# PrototypeVar2_IcChanged.net
KiCad netlist of a schematic drawn in EAGLE
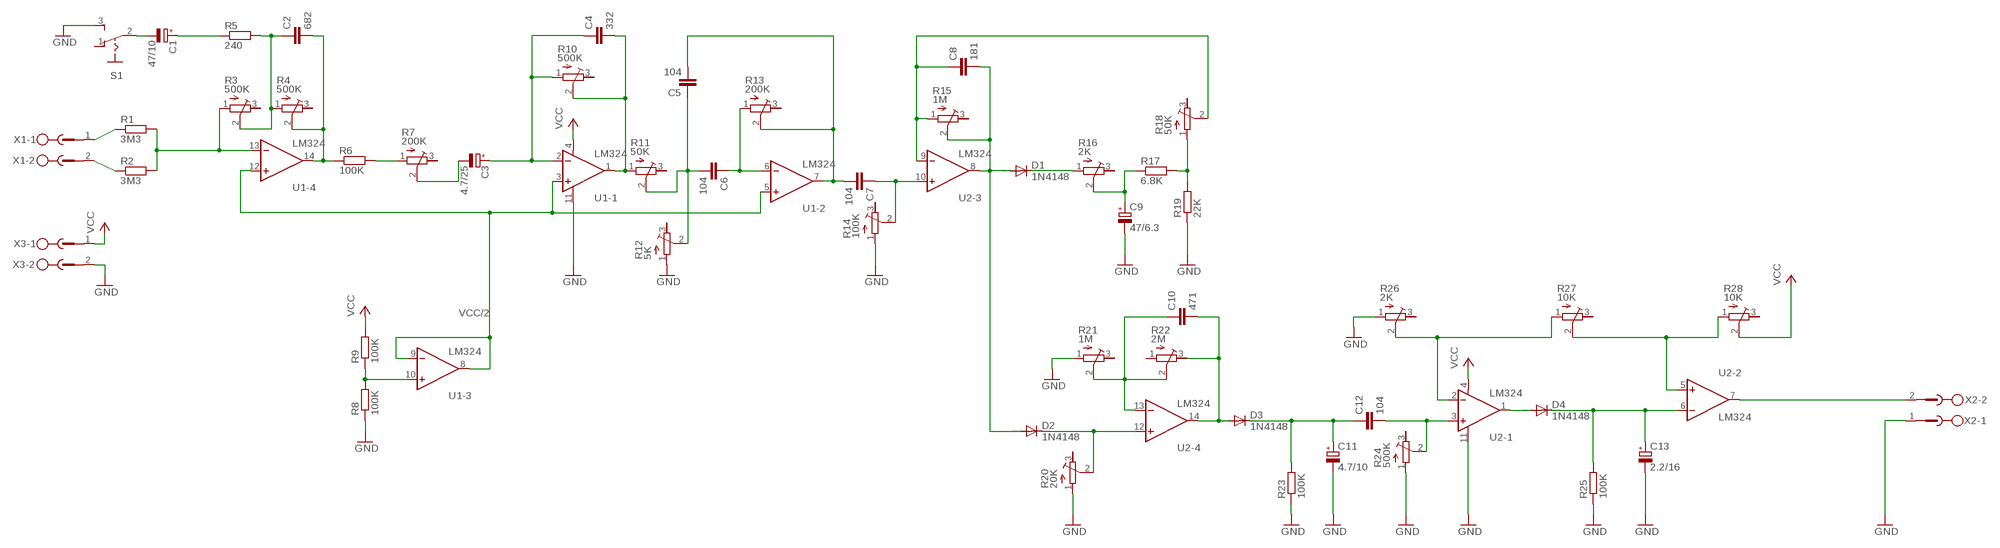
[diagram p0: schematic, sheet 1]

(export (version "E")
  (design (tool "Eeschema 10.0.6"))
  (components
    (comp (ref "C1")
      (value "47/10")
      (footprint "eagle-import:E2,5-7")
      (libsource (lib "eagle-import") (part "CPOL-EUE2.5-7"))
    )
    (comp (ref "C2")
      (value "682")
      (footprint "eagle-import:C050-035X075")
      (libsource (lib "eagle-import") (part "C-EU050-035X075"))
    )
    (comp (ref "C3")
      (value "4.7/25")
      (footprint "eagle-import:E2,5-7")
      (libsource (lib "eagle-import") (part "CPOL-EUE2.5-7"))
    )
    (comp (ref "C4")
      (value "332")
      (footprint "eagle-import:C050-035X075")
      (libsource (lib "eagle-import") (part "C-EU050-035X075"))
    )
    (comp (ref "C5")
      (value "104")
      (footprint "eagle-import:C050-035X075")
      (libsource (lib "eagle-import") (part "C-EU050-035X075"))
    )
    (comp (ref "C6")
      (value "104")
      (footprint "eagle-import:C050-035X075")
      (libsource (lib "eagle-import") (part "C-EU050-035X075"))
    )
    (comp (ref "C7")
      (value "104")
      (footprint "eagle-import:C050-035X075")
      (libsource (lib "eagle-import") (part "C-EU050-035X075"))
    )
    (comp (ref "C8")
      (value "181")
      (footprint "eagle-import:C050-035X075")
      (libsource (lib "eagle-import") (part "C-EU050-035X075"))
    )
    (comp (ref "C9")
      (value "47/6.3")
      (footprint "eagle-import:E2,5-7")
      (libsource (lib "eagle-import") (part "CPOL-EUE2.5-7"))
    )
    (comp (ref "C10")
      (value "471")
      (footprint "eagle-import:C050-035X075")
      (libsource (lib "eagle-import") (part "C-EU050-035X075"))
    )
    (comp (ref "C11")
      (value "4.7/10")
      (footprint "eagle-import:E2,5-7")
      (libsource (lib "eagle-import") (part "CPOL-EUE2.5-7"))
    )
    (comp (ref "C12")
      (value "104")
      (footprint "eagle-import:C050-035X075")
      (libsource (lib "eagle-import") (part "C-EU050-035X075"))
    )
    (comp (ref "C13")
      (value "2.2/16")
      (footprint "eagle-import:E2,5-7")
      (libsource (lib "eagle-import") (part "CPOL-EUE2.5-7"))
    )
    (comp (ref "D1")
      (value "1N4148")
      (footprint "eagle-import:DO35-10")
      (libsource (lib "eagle-import") (part "1N4148DO35-10"))
    )
    (comp (ref "D2")
      (value "1N4148")
      (footprint "eagle-import:DO35-10")
      (libsource (lib "eagle-import") (part "1N4148DO35-10"))
    )
    (comp (ref "D3")
      (value "1N4148")
      (footprint "eagle-import:DO35-10")
      (libsource (lib "eagle-import") (part "1N4148DO35-10"))
    )
    (comp (ref "D4")
      (value "1N4148")
      (footprint "eagle-import:DO35-10")
      (libsource (lib "eagle-import") (part "1N4148DO35-10"))
    )
    (comp (ref "R1")
      (value "3M3")
      (footprint "eagle-import:0204_7")
      (libsource (lib "eagle-import") (part "R-EU_0204/7"))
    )
    (comp (ref "R2")
      (value "3M3")
      (footprint "eagle-import:0204_7")
      (libsource (lib "eagle-import") (part "R-EU_0204/7"))
    )
    (comp (ref "R3")
      (value "500K")
      (footprint "eagle-import:RTRIM64W")
      (libsource (lib "eagle-import") (part "R-TRIMM64W"))
    )
    (comp (ref "R4")
      (value "500K")
      (footprint "eagle-import:RTRIM64W")
      (libsource (lib "eagle-import") (part "R-TRIMM64W"))
    )
    (comp (ref "R5")
      (value "240")
      (footprint "eagle-import:0204_7")
      (libsource (lib "eagle-import") (part "R-EU_0204/7"))
    )
    (comp (ref "R6")
      (value "100K")
      (footprint "eagle-import:0204_7")
      (libsource (lib "eagle-import") (part "R-EU_0204/7"))
    )
    (comp (ref "R7")
      (value "200K")
      (footprint "eagle-import:RTRIM64W")
      (libsource (lib "eagle-import") (part "R-TRIMM64W"))
    )
    (comp (ref "R8")
      (value "100K")
      (footprint "eagle-import:0207_10")
      (libsource (lib "eagle-import") (part "R-EU_0207/10"))
    )
    (comp (ref "R9")
      (value "100K")
      (footprint "eagle-import:0207_10")
      (libsource (lib "eagle-import") (part "R-EU_0207/10"))
    )
    (comp (ref "R10")
      (value "500K")
      (footprint "eagle-import:RTRIM64W")
      (libsource (lib "eagle-import") (part "R-TRIMM64W"))
    )
    (comp (ref "R11")
      (value "50K")
      (footprint "eagle-import:RTRIM64W")
      (libsource (lib "eagle-import") (part "R-TRIMM64W"))
    )
    (comp (ref "R12")
      (value "5K")
      (footprint "eagle-import:RTRIM64W")
      (libsource (lib "eagle-import") (part "R-TRIMM64W"))
    )
    (comp (ref "R13")
      (value "200K")
      (footprint "eagle-import:RTRIM64W")
      (libsource (lib "eagle-import") (part "R-TRIMM64W"))
    )
    (comp (ref "R14")
      (value "100K")
      (footprint "eagle-import:RTRIM64W")
      (libsource (lib "eagle-import") (part "R-TRIMM64W"))
    )
    (comp (ref "R15")
      (value "1M")
      (footprint "eagle-import:RTRIM64W")
      (libsource (lib "eagle-import") (part "R-TRIMM64W"))
    )
    (comp (ref "R16")
      (value "2K")
      (footprint "eagle-import:RTRIM64W")
      (libsource (lib "eagle-import") (part "R-TRIMM64W"))
    )
    (comp (ref "R17")
      (value "6.8K")
      (footprint "eagle-import:0204_7")
      (libsource (lib "eagle-import") (part "R-EU_0204/7"))
    )
    (comp (ref "R18")
      (value "50K")
      (footprint "eagle-import:RTRIM64W")
      (libsource (lib "eagle-import") (part "R-TRIMM64W"))
    )
    (comp (ref "R19")
      (value "22K")
      (footprint "eagle-import:0204_7")
      (libsource (lib "eagle-import") (part "R-EU_0204/7"))
    )
    (comp (ref "R20")
      (value "20K")
      (footprint "eagle-import:RTRIM64W")
      (libsource (lib "eagle-import") (part "R-TRIMM64W"))
    )
    (comp (ref "R21")
      (value "1M")
      (footprint "eagle-import:RTRIM64W")
      (libsource (lib "eagle-import") (part "R-TRIMM64W"))
    )
    (comp (ref "R22")
      (value "2M")
      (footprint "eagle-import:RTRIM64W")
      (libsource (lib "eagle-import") (part "R-TRIMM64W"))
    )
    (comp (ref "R23")
      (value "100K")
      (footprint "eagle-import:0204_7")
      (libsource (lib "eagle-import") (part "R-EU_0204/7"))
    )
    (comp (ref "R24")
      (value "500K")
      (footprint "eagle-import:RTRIM64W")
      (libsource (lib "eagle-import") (part "R-TRIMM64W"))
    )
    (comp (ref "R25")
      (value "100K")
      (footprint "eagle-import:0204_7")
      (libsource (lib "eagle-import") (part "R-EU_0204/7"))
    )
    (comp (ref "R26")
      (value "2K")
      (footprint "eagle-import:RTRIM64W")
      (libsource (lib "eagle-import") (part "R-TRIMM64W"))
    )
    (comp (ref "R27")
      (value "10K")
      (footprint "eagle-import:RTRIM64W")
      (libsource (lib "eagle-import") (part "R-TRIMM64W"))
    )
    (comp (ref "R28")
      (value "10K")
      (footprint "eagle-import:RTRIM64W")
      (libsource (lib "eagle-import") (part "R-TRIMM64W"))
    )
    (comp (ref "S1")
      (value "255SB")
      (footprint "eagle-import:255SB")
      (libsource (lib "eagle-import") (part "255SB"))
    )
    (comp (ref "U1-")
      (value "LM324")
      (footprint "eagle-import:SOIC-14")
      (libsource (lib "eagle-import") (part "LM324"))
    )
    (comp (ref "U2-")
      (value "LM324")
      (footprint "eagle-import:SOIC-14")
      (libsource (lib "eagle-import") (part "LM324"))
    )
    (comp (ref "X1")
      (value "MSTBV2")
      (footprint "eagle-import:MSTBV2")
      (libsource (lib "eagle-import") (part "MSTBV2"))
    )
    (comp (ref "X2")
      (value "MSTBV2")
      (footprint "eagle-import:MSTBV2")
      (libsource (lib "eagle-import") (part "MSTBV2"))
    )
    (comp (ref "X3")
      (value "MSTBV2")
      (footprint "eagle-import:MSTBV2")
      (libsource (lib "eagle-import") (part "MSTBV2"))
    )
  )
  (nets
    (net (code "1") (name "/VCC{slash}2") (class "Default")
      (node (ref "U1-") (pin "12") (pinfunction "+IN_12") (pintype "input"))
      (node (ref "U1-") (pin "3") (pinfunction "+IN_3") (pintype "input"))
      (node (ref "U1-") (pin "5") (pinfunction "+IN_5") (pintype "input"))
      (node (ref "U1-") (pin "8") (pinfunction "OUT_8") (pintype "output"))
      (node (ref "U1-") (pin "9") (pinfunction "-IN_9") (pintype "input"))
    )
    (net (code "2") (name "GND") (class "Default")
      (node (ref "C11") (pin "-") (pinfunction "-_-") (pintype "passive"))
      (node (ref "C13") (pin "-") (pinfunction "-_-") (pintype "passive"))
      (node (ref "C9") (pin "-") (pinfunction "-_-") (pintype "passive"))
      (node (ref "R12") (pin "1") (pinfunction "A_1") (pintype "passive"))
      (node (ref "R14") (pin "1") (pinfunction "A_1") (pintype "passive"))
      (node (ref "R19") (pin "1") (pinfunction "1_1") (pintype "passive"))
      (node (ref "R20") (pin "1") (pinfunction "A_1") (pintype "passive"))
      (node (ref "R21") (pin "1") (pinfunction "A_1") (pintype "passive"))
      (node (ref "R23") (pin "1") (pinfunction "1_1") (pintype "passive"))
      (node (ref "R24") (pin "1") (pinfunction "A_1") (pintype "passive"))
      (node (ref "R25") (pin "1") (pinfunction "1_1") (pintype "passive"))
      (node (ref "R26") (pin "1") (pinfunction "A_1") (pintype "passive"))
      (node (ref "R8") (pin "1") (pinfunction "1_1") (pintype "passive"))
      (node (ref "S1") (pin "3") (pinfunction "S_3") (pintype "passive"))
      (node (ref "U1-") (pin "11") (pinfunction "V-_11") (pintype "power_in"))
      (node (ref "U2-") (pin "11") (pinfunction "V-_11") (pintype "power_in"))
      (node (ref "X2") (pin "1") (pinfunction "SK_1") (pintype "passive"))
      (node (ref "X3") (pin "2") (pinfunction "SK_2") (pintype "passive"))
    )
    (net (code "3") (name "Net-(C1-Pad+)") (class "Default")
      (node (ref "C1") (pin "+") (pinfunction "+_+") (pintype "passive"))
      (node (ref "R5") (pin "1") (pinfunction "1_1") (pintype "passive"))
    )
    (net (code "4") (name "Net-(C11-Pad+)") (class "Default")
      (node (ref "C11") (pin "+") (pinfunction "+_+") (pintype "passive"))
      (node (ref "C12") (pin "1") (pinfunction "1_1") (pintype "passive"))
      (node (ref "D3") (pin "C") (pinfunction "C_C") (pintype "passive"))
      (node (ref "R23") (pin "2") (pinfunction "2_2") (pintype "passive"))
    )
    (net (code "5") (name "Net-(R3-A)") (class "Default")
      (node (ref "R1") (pin "2") (pinfunction "2_2") (pintype "passive"))
      (node (ref "R2") (pin "2") (pinfunction "2_2") (pintype "passive"))
      (node (ref "R3") (pin "1") (pinfunction "A_1") (pintype "passive"))
      (node (ref "U1-") (pin "13") (pinfunction "-IN_13") (pintype "input"))
    )
    (net (code "6") (name "Net-(R3-S)") (class "Default")
      (node (ref "C2") (pin "1") (pinfunction "1_1") (pintype "passive"))
      (node (ref "R3") (pin "2") (pinfunction "S_2") (pintype "passive"))
      (node (ref "R4") (pin "1") (pinfunction "A_1") (pintype "passive"))
      (node (ref "R5") (pin "2") (pinfunction "2_2") (pintype "passive"))
    )
    (net (code "7") (name "Net-(R4-S)") (class "Default")
      (node (ref "C2") (pin "2") (pinfunction "2_2") (pintype "passive"))
      (node (ref "R4") (pin "2") (pinfunction "S_2") (pintype "passive"))
      (node (ref "R6") (pin "1") (pinfunction "1_1") (pintype "passive"))
      (node (ref "U1-") (pin "14") (pinfunction "OUT_14") (pintype "output"))
    )
    (net (code "8") (name "Net-(R7-A)") (class "Default")
      (node (ref "R6") (pin "2") (pinfunction "2_2") (pintype "passive"))
      (node (ref "R7") (pin "1") (pinfunction "A_1") (pintype "passive"))
    )
    (net (code "9") (name "Net-(R7-S)") (class "Default")
      (node (ref "C3") (pin "-") (pinfunction "-_-") (pintype "passive"))
      (node (ref "R7") (pin "2") (pinfunction "S_2") (pintype "passive"))
    )
    (net (code "10") (name "Net-(R10-A)") (class "Default")
      (node (ref "C3") (pin "+") (pinfunction "+_+") (pintype "passive"))
      (node (ref "C4") (pin "1") (pinfunction "1_1") (pintype "passive"))
      (node (ref "R10") (pin "1") (pinfunction "A_1") (pintype "passive"))
      (node (ref "U1-") (pin "2") (pinfunction "-IN_2") (pintype "input"))
    )
    (net (code "11") (name "Net-(R10-S)") (class "Default")
      (node (ref "C4") (pin "2") (pinfunction "2_2") (pintype "passive"))
      (node (ref "R10") (pin "2") (pinfunction "S_2") (pintype "passive"))
      (node (ref "R11") (pin "1") (pinfunction "A_1") (pintype "passive"))
      (node (ref "U1-") (pin "1") (pinfunction "OUT_1") (pintype "output"))
    )
    (net (code "12") (name "Net-(R11-S)") (class "Default")
      (node (ref "C5") (pin "1") (pinfunction "1_1") (pintype "passive"))
      (node (ref "C6") (pin "2") (pinfunction "2_2") (pintype "passive"))
      (node (ref "R11") (pin "2") (pinfunction "S_2") (pintype "passive"))
      (node (ref "R12") (pin "2") (pinfunction "S_2") (pintype "passive"))
    )
    (net (code "13") (name "Net-(R13-A)") (class "Default")
      (node (ref "C6") (pin "1") (pinfunction "1_1") (pintype "passive"))
      (node (ref "R13") (pin "1") (pinfunction "A_1") (pintype "passive"))
      (node (ref "U1-") (pin "6") (pinfunction "-IN_6") (pintype "input"))
    )
    (net (code "14") (name "Net-(R13-S)") (class "Default")
      (node (ref "C5") (pin "2") (pinfunction "2_2") (pintype "passive"))
      (node (ref "C7") (pin "2") (pinfunction "2_2") (pintype "passive"))
      (node (ref "R13") (pin "2") (pinfunction "S_2") (pintype "passive"))
      (node (ref "U1-") (pin "7") (pinfunction "OUT_7") (pintype "output"))
    )
    (net (code "15") (name "Net-(R14-S)") (class "Default")
      (node (ref "C7") (pin "1") (pinfunction "1_1") (pintype "passive"))
      (node (ref "R14") (pin "2") (pinfunction "S_2") (pintype "passive"))
      (node (ref "U2-") (pin "10") (pinfunction "+IN_10") (pintype "input"))
    )
    (net (code "16") (name "Net-(R15-A)") (class "Default")
      (node (ref "C8") (pin "1") (pinfunction "1_1") (pintype "passive"))
      (node (ref "R15") (pin "1") (pinfunction "A_1") (pintype "passive"))
      (node (ref "R18") (pin "2") (pinfunction "S_2") (pintype "passive"))
      (node (ref "U2-") (pin "9") (pinfunction "-IN_9") (pintype "input"))
    )
    (net (code "17") (name "Net-(R15-S)") (class "Default")
      (node (ref "C8") (pin "2") (pinfunction "2_2") (pintype "passive"))
      (node (ref "D1") (pin "A") (pinfunction "A_A") (pintype "passive"))
      (node (ref "D2") (pin "A") (pinfunction "A_A") (pintype "passive"))
      (node (ref "R15") (pin "2") (pinfunction "S_2") (pintype "passive"))
      (node (ref "U2-") (pin "8") (pinfunction "OUT_8") (pintype "output"))
    )
    (net (code "18") (name "Net-(R16-A)") (class "Default")
      (node (ref "D1") (pin "C") (pinfunction "C_C") (pintype "passive"))
      (node (ref "R16") (pin "1") (pinfunction "A_1") (pintype "passive"))
    )
    (net (code "19") (name "Net-(R16-S)") (class "Default")
      (node (ref "C9") (pin "+") (pinfunction "+_+") (pintype "passive"))
      (node (ref "R16") (pin "2") (pinfunction "S_2") (pintype "passive"))
      (node (ref "R17") (pin "1") (pinfunction "1_1") (pintype "passive"))
    )
    (net (code "20") (name "Net-(R18-A)") (class "Default")
      (node (ref "R17") (pin "2") (pinfunction "2_2") (pintype "passive"))
      (node (ref "R18") (pin "1") (pinfunction "A_1") (pintype "passive"))
      (node (ref "R19") (pin "2") (pinfunction "2_2") (pintype "passive"))
    )
    (net (code "21") (name "Net-(R20-S)") (class "Default")
      (node (ref "D2") (pin "C") (pinfunction "C_C") (pintype "passive"))
      (node (ref "R20") (pin "2") (pinfunction "S_2") (pintype "passive"))
      (node (ref "U2-") (pin "12") (pinfunction "+IN_12") (pintype "input"))
    )
    (net (code "22") (name "Net-(R21-S)") (class "Default")
      (node (ref "C10") (pin "1") (pinfunction "1_1") (pintype "passive"))
      (node (ref "R21") (pin "2") (pinfunction "S_2") (pintype "passive"))
      (node (ref "R22") (pin "2") (pinfunction "S_2") (pintype "passive"))
      (node (ref "U2-") (pin "13") (pinfunction "-IN_13") (pintype "input"))
    )
    (net (code "23") (name "Net-(R22-E)") (class "Default")
      (node (ref "C10") (pin "2") (pinfunction "2_2") (pintype "passive"))
      (node (ref "D3") (pin "A") (pinfunction "A_A") (pintype "passive"))
      (node (ref "R22") (pin "3") (pinfunction "E_3") (pintype "passive"))
      (node (ref "U2-") (pin "14") (pinfunction "OUT_14") (pintype "output"))
    )
    (net (code "24") (name "Net-(R24-S)") (class "Default")
      (node (ref "C12") (pin "2") (pinfunction "2_2") (pintype "passive"))
      (node (ref "R24") (pin "2") (pinfunction "S_2") (pintype "passive"))
      (node (ref "U2-") (pin "3") (pinfunction "+IN_3") (pintype "input"))
    )
    (net (code "25") (name "Net-(R26-S)") (class "Default")
      (node (ref "R26") (pin "2") (pinfunction "S_2") (pintype "passive"))
      (node (ref "R27") (pin "1") (pinfunction "A_1") (pintype "passive"))
      (node (ref "U2-") (pin "2") (pinfunction "-IN_2") (pintype "input"))
    )
    (net (code "26") (name "Net-(R27-S)") (class "Default")
      (node (ref "R27") (pin "2") (pinfunction "S_2") (pintype "passive"))
      (node (ref "R28") (pin "1") (pinfunction "A_1") (pintype "passive"))
      (node (ref "U2-") (pin "5") (pinfunction "+IN_5") (pintype "input"))
    )
    (net (code "27") (name "Net-(S1-P)") (class "Default")
      (node (ref "C1") (pin "-") (pinfunction "-_-") (pintype "passive"))
      (node (ref "S1") (pin "2") (pinfunction "P_2") (pintype "passive"))
    )
    (net (code "28") (name "Net-(U1-C-+IN)") (class "Default")
      (node (ref "R8") (pin "2") (pinfunction "2_2") (pintype "passive"))
      (node (ref "R9") (pin "1") (pinfunction "1_1") (pintype "passive"))
      (node (ref "U1-") (pin "10") (pinfunction "+IN_10") (pintype "input"))
    )
    (net (code "29") (name "Net-(U2-A-OUT)") (class "Default")
      (node (ref "D4") (pin "A") (pinfunction "A_A") (pintype "passive"))
      (node (ref "U2-") (pin "1") (pinfunction "OUT_1") (pintype "output"))
    )
    (net (code "30") (name "Net-(U2-B--IN)") (class "Default")
      (node (ref "C13") (pin "+") (pinfunction "+_+") (pintype "passive"))
      (node (ref "D4") (pin "C") (pinfunction "C_C") (pintype "passive"))
      (node (ref "R25") (pin "2") (pinfunction "2_2") (pintype "passive"))
      (node (ref "U2-") (pin "6") (pinfunction "-IN_6") (pintype "input"))
    )
    (net (code "31") (name "Net-(U2-B-OUT)") (class "Default")
      (node (ref "U2-") (pin "7") (pinfunction "OUT_7") (pintype "output"))
      (node (ref "X2") (pin "2") (pinfunction "SK_2") (pintype "passive"))
    )
    (net (code "32") (name "Net-(X1A-SK)") (class "Default")
      (node (ref "R1") (pin "1") (pinfunction "1_1") (pintype "passive"))
      (node (ref "X1") (pin "1") (pinfunction "SK_1") (pintype "passive"))
    )
    (net (code "33") (name "Net-(X1B-SK)") (class "Default")
      (node (ref "R2") (pin "1") (pinfunction "1_1") (pintype "passive"))
      (node (ref "X1") (pin "2") (pinfunction "SK_2") (pintype "passive"))
    )
    (net (code "34") (name "VCC") (class "Default")
      (node (ref "R28") (pin "2") (pinfunction "S_2") (pintype "passive"))
      (node (ref "R9") (pin "2") (pinfunction "2_2") (pintype "passive"))
      (node (ref "U1-") (pin "4") (pinfunction "V+_4") (pintype "power_in"))
      (node (ref "U2-") (pin "4") (pinfunction "V+_4") (pintype "power_in"))
      (node (ref "X3") (pin "1") (pinfunction "SK_1") (pintype "passive"))
    )
    (net (code "35") (name "unconnected-(R3-E-Pad3)") (class "Default")
      (node (ref "R3") (pin "3") (pinfunction "E_3") (pintype "passive"))
    )
    (net (code "36") (name "unconnected-(R4-E-Pad3)") (class "Default")
      (node (ref "R4") (pin "3") (pinfunction "E_3") (pintype "passive"))
    )
    (net (code "37") (name "unconnected-(R7-E-Pad3)") (class "Default")
      (node (ref "R7") (pin "3") (pinfunction "E_3") (pintype "passive"))
    )
    (net (code "38") (name "unconnected-(R10-E-Pad3)") (class "Default")
      (node (ref "R10") (pin "3") (pinfunction "E_3") (pintype "passive"))
    )
    (net (code "39") (name "unconnected-(R11-E-Pad3)") (class "Default")
      (node (ref "R11") (pin "3") (pinfunction "E_3") (pintype "passive"))
    )
    (net (code "40") (name "unconnected-(R12-E-Pad3)") (class "Default")
      (node (ref "R12") (pin "3") (pinfunction "E_3") (pintype "passive"))
    )
    (net (code "41") (name "unconnected-(R13-E-Pad3)") (class "Default")
      (node (ref "R13") (pin "3") (pinfunction "E_3") (pintype "passive"))
    )
    (net (code "42") (name "unconnected-(R14-E-Pad3)") (class "Default")
      (node (ref "R14") (pin "3") (pinfunction "E_3") (pintype "passive"))
    )
    (net (code "43") (name "unconnected-(R15-E-Pad3)") (class "Default")
      (node (ref "R15") (pin "3") (pinfunction "E_3") (pintype "passive"))
    )
    (net (code "44") (name "unconnected-(R16-E-Pad3)") (class "Default")
      (node (ref "R16") (pin "3") (pinfunction "E_3") (pintype "passive"))
    )
    (net (code "45") (name "unconnected-(R18-E-Pad3)") (class "Default")
      (node (ref "R18") (pin "3") (pinfunction "E_3") (pintype "passive"))
    )
    (net (code "46") (name "unconnected-(R20-E-Pad3)") (class "Default")
      (node (ref "R20") (pin "3") (pinfunction "E_3") (pintype "passive"))
    )
    (net (code "47") (name "unconnected-(R21-E-Pad3)") (class "Default")
      (node (ref "R21") (pin "3") (pinfunction "E_3") (pintype "passive"))
    )
    (net (code "48") (name "unconnected-(R22-A-Pad1)") (class "Default")
      (node (ref "R22") (pin "1") (pinfunction "A_1") (pintype "passive"))
    )
    (net (code "49") (name "unconnected-(R24-E-Pad3)") (class "Default")
      (node (ref "R24") (pin "3") (pinfunction "E_3") (pintype "passive"))
    )
    (net (code "50") (name "unconnected-(R26-E-Pad3)") (class "Default")
      (node (ref "R26") (pin "3") (pinfunction "E_3") (pintype "passive"))
    )
    (net (code "51") (name "unconnected-(R27-E-Pad3)") (class "Default")
      (node (ref "R27") (pin "3") (pinfunction "E_3") (pintype "passive"))
    )
    (net (code "52") (name "unconnected-(R28-E-Pad3)") (class "Default")
      (node (ref "R28") (pin "3") (pinfunction "E_3") (pintype "passive"))
    )
    (net (code "53") (name "unconnected-(S1-O-Pad1)") (class "Default")
      (node (ref "S1") (pin "1") (pinfunction "O_1") (pintype "passive"))
    )
  )
)
